# PCB_Plates_Combined_Eagle.net
KiCad netlist of a schematic drawn in EAGLE
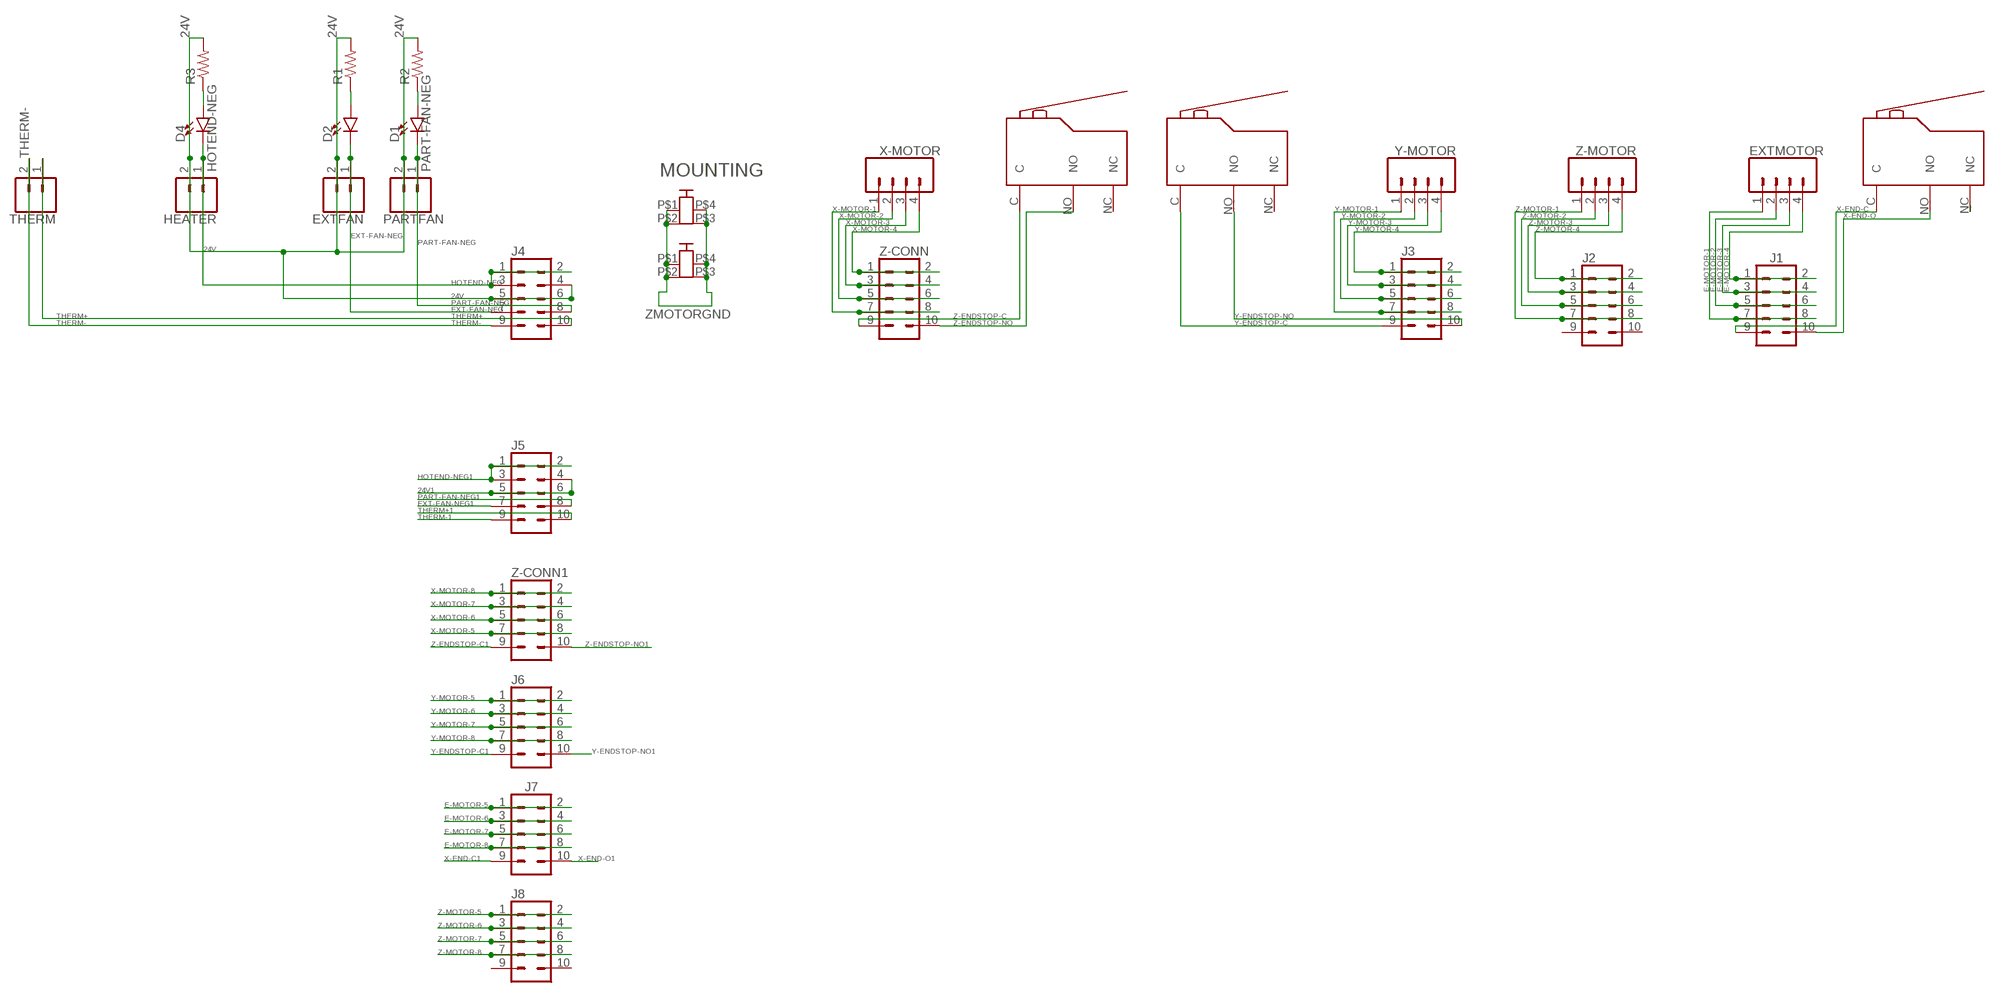
[diagram p0: schematic, sheet 1]

(export (version "E")
  (design (tool "Eeschema 10.0.6"))
  (components
    (comp (ref "CON1")
      (value "PCB-2M3")
      (footprint "eagle-import:PCB2-M3")
      (libsource (lib "eagle-import") (part "PCB-2M3"))
    )
    (comp (ref "CON7")
      (value "PCB-2M3")
      (footprint "eagle-import:PCB2-M3")
      (libsource (lib "eagle-import") (part "PCB-2M3"))
    )
    (comp (ref "D1")
      (value "LED-FKIT-1206")
      (footprint "eagle-import:FKIT-LED-1206")
      (libsource (lib "eagle-import") (part "LED-FKIT-1206"))
    )
    (comp (ref "D2")
      (value "LED-FKIT-1206")
      (footprint "eagle-import:FKIT-LED-1206")
      (libsource (lib "eagle-import") (part "LED-FKIT-1206"))
    )
    (comp (ref "D4")
      (value "LED-FKIT-1206")
      (footprint "eagle-import:FKIT-LED-1206")
      (libsource (lib "eagle-import") (part "LED-FKIT-1206"))
    )
    (comp (ref "EXTFAN")
      (value "CONN_023.5MM_LOCK")
      (footprint "eagle-import:SCREWTERMINAL-3.5MM-2_LOCK")
      (libsource (lib "eagle-import") (part "CONN_023.5MM_LOCK"))
    )
    (comp (ref "EXTMOTOR")
      (value "CONN_04SCREW_LOCK")
      (footprint "eagle-import:SCREWTERMINAL-3.5MM-4_LOCK")
      (libsource (lib "eagle-import") (part "CONN_04SCREW_LOCK"))
    )
    (comp (ref "HEATER")
      (value "CONN_023.5MM_LOCK")
      (footprint "eagle-import:SCREWTERMINAL-3.5MM-2_LOCK")
      (libsource (lib "eagle-import") (part "CONN_023.5MM_LOCK"))
    )
    (comp (ref "J1")
      (value "CONN_05X2SHD_LOCK")
      (footprint "eagle-import:2X5-SHROUDED_LOCK")
      (libsource (lib "eagle-import") (part "CONN_05X2SHD_LOCK"))
    )
    (comp (ref "J2")
      (value "CONN_05X2SHD_LOCK")
      (footprint "eagle-import:2X5-SHROUDED_LOCK")
      (libsource (lib "eagle-import") (part "CONN_05X2SHD_LOCK"))
    )
    (comp (ref "J3")
      (value "CONN_05X2SHD_LOCK")
      (footprint "eagle-import:2X5-SHROUDED_LOCK")
      (libsource (lib "eagle-import") (part "CONN_05X2SHD_LOCK"))
    )
    (comp (ref "J4")
      (value "CONN_05X2SHD_LOCK")
      (footprint "eagle-import:2X5-SHROUDED_LOCK")
      (libsource (lib "eagle-import") (part "CONN_05X2SHD_LOCK"))
    )
    (comp (ref "J5")
      (value "CONN_05X2SHD_LOCK")
      (footprint "eagle-import:2X5-SHROUDED_LOCK")
      (libsource (lib "eagle-import") (part "CONN_05X2SHD_LOCK"))
    )
    (comp (ref "J6")
      (value "CONN_05X2SHD_LOCK")
      (footprint "eagle-import:2X5-SHROUDED_LOCK")
      (libsource (lib "eagle-import") (part "CONN_05X2SHD_LOCK"))
    )
    (comp (ref "J7")
      (value "CONN_05X2SHD_LOCK")
      (footprint "eagle-import:2X5-SHROUDED_LOCK")
      (libsource (lib "eagle-import") (part "CONN_05X2SHD_LOCK"))
    )
    (comp (ref "J8")
      (value "CONN_05X2SHD_LOCK")
      (footprint "eagle-import:2X5-SHROUDED_LOCK")
      (libsource (lib "eagle-import") (part "CONN_05X2SHD_LOCK"))
    )
    (comp (ref "PARTFAN")
      (value "CONN_023.5MM_LOCK")
      (footprint "eagle-import:SCREWTERMINAL-3.5MM-2_LOCK")
      (libsource (lib "eagle-import") (part "CONN_023.5MM_LOCK"))
    )
    (comp (ref "R1")
      (value "R-US_R1206")
      (footprint "eagle-import:R1206")
      (libsource (lib "eagle-import") (part "R-US_R1206"))
    )
    (comp (ref "R2")
      (value "R-US_R1206")
      (footprint "eagle-import:R1206")
      (libsource (lib "eagle-import") (part "R-US_R1206"))
    )
    (comp (ref "R3")
      (value "R-US_R1206")
      (footprint "eagle-import:R1206")
      (libsource (lib "eagle-import") (part "R-US_R1206"))
    )
    (comp (ref "THERM")
      (value "CONN_023.5MM_LOCK")
      (footprint "eagle-import:SCREWTERMINAL-3.5MM-2_LOCK")
      (libsource (lib "eagle-import") (part "CONN_023.5MM_LOCK"))
    )
    (comp (ref "U$1")
      (value "Lever Microswitch Leftangle PCB mount, with Roller style lever, with a red roller")
      (footprint "eagle-import:LEVERMICROPCB-LEFTANGLE")
      (libsource (lib "eagle-import") (part "LEVERMICROPCBLEFTANGLE"))
    )
    (comp (ref "X-MOTOR")
      (value "CONN_04SCREW_LOCK")
      (footprint "eagle-import:SCREWTERMINAL-3.5MM-4_LOCK")
      (libsource (lib "eagle-import") (part "CONN_04SCREW_LOCK"))
    )
    (comp (ref "XENDSTOP")
      (value "Lever Microswitch Leftangle PCB mount, with Roller style lever, with a red roller")
      (footprint "eagle-import:LEVERMICROPCB-LEFTANGLE")
      (libsource (lib "eagle-import") (part "LEVERMICROPCBLEFTANGLE"))
    )
    (comp (ref "Y-MOTOR")
      (value "CONN_04SCREW_LOCK")
      (footprint "eagle-import:SCREWTERMINAL-3.5MM-4_LOCK")
      (libsource (lib "eagle-import") (part "CONN_04SCREW_LOCK"))
    )
    (comp (ref "Z-CONN")
      (value "CONN_05X2SHD_LOCK")
      (footprint "eagle-import:2X5-SHROUDED_LOCK")
      (libsource (lib "eagle-import") (part "CONN_05X2SHD_LOCK"))
    )
    (comp (ref "Z-CONN1")
      (value "CONN_05X2SHD_LOCK")
      (footprint "eagle-import:2X5-SHROUDED_LOCK")
      (libsource (lib "eagle-import") (part "CONN_05X2SHD_LOCK"))
    )
    (comp (ref "Z-MOTOR")
      (value "CONN_04SCREW_LOCK")
      (footprint "eagle-import:SCREWTERMINAL-3.5MM-4_LOCK")
      (libsource (lib "eagle-import") (part "CONN_04SCREW_LOCK"))
    )
    (comp (ref "ZENDSTOP")
      (value "Lever Microswitch Leftangle PCB mount, with Roller style lever, with a red roller")
      (footprint "eagle-import:LEVERMICROPCB-LEFTANGLE")
      (libsource (lib "eagle-import") (part "LEVERMICROPCBLEFTANGLE"))
    )
  )
  (nets
    (net (code "1") (name "/24V") (class "Default")
      (node (ref "EXTFAN") (pin "2") (pinfunction "2_2") (pintype "passive"))
      (node (ref "HEATER") (pin "2") (pinfunction "2_2") (pintype "passive"))
      (node (ref "J4") (pin "4") (pinfunction "4_4") (pintype "passive"))
      (node (ref "J4") (pin "5") (pinfunction "5_5") (pintype "passive"))
      (node (ref "J4") (pin "6") (pinfunction "6_6") (pintype "passive"))
      (node (ref "PARTFAN") (pin "2") (pinfunction "2_2") (pintype "passive"))
      (node (ref "R1") (pin "2") (pinfunction "2_2") (pintype "passive"))
      (node (ref "R2") (pin "2") (pinfunction "2_2") (pintype "passive"))
      (node (ref "R3") (pin "2") (pinfunction "2_2") (pintype "passive"))
    )
    (net (code "2") (name "/24V1") (class "Default")
      (node (ref "J5") (pin "4") (pinfunction "4_4") (pintype "passive"))
      (node (ref "J5") (pin "5") (pinfunction "5_5") (pintype "passive"))
      (node (ref "J5") (pin "6") (pinfunction "6_6") (pintype "passive"))
    )
    (net (code "3") (name "/E-MOTOR-1") (class "Default")
      (node (ref "EXTMOTOR") (pin "1") (pinfunction "1_1") (pintype "passive"))
      (node (ref "J1") (pin "7") (pinfunction "7_7") (pintype "passive"))
      (node (ref "J1") (pin "8") (pinfunction "8_8") (pintype "passive"))
    )
    (net (code "4") (name "/E-MOTOR-2") (class "Default")
      (node (ref "EXTMOTOR") (pin "2") (pinfunction "2_2") (pintype "passive"))
      (node (ref "J1") (pin "5") (pinfunction "5_5") (pintype "passive"))
      (node (ref "J1") (pin "6") (pinfunction "6_6") (pintype "passive"))
    )
    (net (code "5") (name "/E-MOTOR-3") (class "Default")
      (node (ref "EXTMOTOR") (pin "3") (pinfunction "3_3") (pintype "passive"))
      (node (ref "J1") (pin "3") (pinfunction "3_3") (pintype "passive"))
      (node (ref "J1") (pin "4") (pinfunction "4_4") (pintype "passive"))
    )
    (net (code "6") (name "/E-MOTOR-4") (class "Default")
      (node (ref "EXTMOTOR") (pin "4") (pinfunction "4_4") (pintype "passive"))
      (node (ref "J1") (pin "1") (pinfunction "1_1") (pintype "passive"))
      (node (ref "J1") (pin "2") (pinfunction "2_2") (pintype "passive"))
    )
    (net (code "7") (name "/E-MOTOR-5") (class "Default")
      (node (ref "J7") (pin "1") (pinfunction "1_1") (pintype "passive"))
      (node (ref "J7") (pin "2") (pinfunction "2_2") (pintype "passive"))
    )
    (net (code "8") (name "/E-MOTOR-6") (class "Default")
      (node (ref "J7") (pin "3") (pinfunction "3_3") (pintype "passive"))
      (node (ref "J7") (pin "4") (pinfunction "4_4") (pintype "passive"))
    )
    (net (code "9") (name "/E-MOTOR-7") (class "Default")
      (node (ref "J7") (pin "5") (pinfunction "5_5") (pintype "passive"))
      (node (ref "J7") (pin "6") (pinfunction "6_6") (pintype "passive"))
    )
    (net (code "10") (name "/E-MOTOR-8") (class "Default")
      (node (ref "J7") (pin "7") (pinfunction "7_7") (pintype "passive"))
      (node (ref "J7") (pin "8") (pinfunction "8_8") (pintype "passive"))
    )
    (net (code "11") (name "/EXT-FAN-NEG") (class "Default")
      (node (ref "D2") (pin "C") (pinfunction "C_C") (pintype "passive"))
      (node (ref "EXTFAN") (pin "1") (pinfunction "1_1") (pintype "passive"))
      (node (ref "J4") (pin "7") (pinfunction "7_7") (pintype "passive"))
    )
    (net (code "12") (name "/EXT-FAN-NEG1") (class "Default")
      (node (ref "J5") (pin "7") (pinfunction "7_7") (pintype "passive"))
    )
    (net (code "13") (name "/HOTEND-NEG") (class "Default")
      (node (ref "D4") (pin "C") (pinfunction "C_C") (pintype "passive"))
      (node (ref "HEATER") (pin "1") (pinfunction "1_1") (pintype "passive"))
      (node (ref "J4") (pin "1") (pinfunction "1_1") (pintype "passive"))
      (node (ref "J4") (pin "2") (pinfunction "2_2") (pintype "passive"))
      (node (ref "J4") (pin "3") (pinfunction "3_3") (pintype "passive"))
    )
    (net (code "14") (name "/HOTEND-NEG1") (class "Default")
      (node (ref "J5") (pin "1") (pinfunction "1_1") (pintype "passive"))
      (node (ref "J5") (pin "2") (pinfunction "2_2") (pintype "passive"))
      (node (ref "J5") (pin "3") (pinfunction "3_3") (pintype "passive"))
    )
    (net (code "15") (name "/PART-FAN-NEG") (class "Default")
      (node (ref "D1") (pin "C") (pinfunction "C_C") (pintype "passive"))
      (node (ref "J4") (pin "8") (pinfunction "8_8") (pintype "passive"))
      (node (ref "PARTFAN") (pin "1") (pinfunction "1_1") (pintype "passive"))
    )
    (net (code "16") (name "/PART-FAN-NEG1") (class "Default")
      (node (ref "J5") (pin "8") (pinfunction "8_8") (pintype "passive"))
    )
    (net (code "17") (name "/THERM+") (class "Default")
      (node (ref "J4") (pin "10") (pinfunction "10_10") (pintype "passive"))
      (node (ref "THERM") (pin "1") (pinfunction "1_1") (pintype "passive"))
    )
    (net (code "18") (name "/THERM+1") (class "Default")
      (node (ref "J5") (pin "10") (pinfunction "10_10") (pintype "passive"))
    )
    (net (code "19") (name "/THERM-") (class "Default")
      (node (ref "J4") (pin "9") (pinfunction "9_9") (pintype "passive"))
      (node (ref "THERM") (pin "2") (pinfunction "2_2") (pintype "passive"))
    )
    (net (code "20") (name "/THERM-1") (class "Default")
      (node (ref "J5") (pin "9") (pinfunction "9_9") (pintype "passive"))
    )
    (net (code "21") (name "/X-END-C") (class "Default")
      (node (ref "J1") (pin "9") (pinfunction "9_9") (pintype "passive"))
      (node (ref "XENDSTOP") (pin "C") (pinfunction "C_C") (pintype "bidirectional"))
    )
    (net (code "22") (name "/X-END-C1") (class "Default")
      (node (ref "J7") (pin "9") (pinfunction "9_9") (pintype "passive"))
    )
    (net (code "23") (name "/X-END-O") (class "Default")
      (node (ref "J1") (pin "10") (pinfunction "10_10") (pintype "passive"))
      (node (ref "XENDSTOP") (pin "NO") (pinfunction "NO_NO") (pintype "bidirectional"))
    )
    (net (code "24") (name "/X-END-O1") (class "Default")
      (node (ref "J7") (pin "10") (pinfunction "10_10") (pintype "passive"))
    )
    (net (code "25") (name "/X-MOTOR-1") (class "Default")
      (node (ref "X-MOTOR") (pin "1") (pinfunction "1_1") (pintype "passive"))
      (node (ref "Z-CONN") (pin "7") (pinfunction "7_7") (pintype "passive"))
      (node (ref "Z-CONN") (pin "8") (pinfunction "8_8") (pintype "passive"))
    )
    (net (code "26") (name "/X-MOTOR-2") (class "Default")
      (node (ref "X-MOTOR") (pin "2") (pinfunction "2_2") (pintype "passive"))
      (node (ref "Z-CONN") (pin "5") (pinfunction "5_5") (pintype "passive"))
      (node (ref "Z-CONN") (pin "6") (pinfunction "6_6") (pintype "passive"))
    )
    (net (code "27") (name "/X-MOTOR-3") (class "Default")
      (node (ref "X-MOTOR") (pin "3") (pinfunction "3_3") (pintype "passive"))
      (node (ref "Z-CONN") (pin "3") (pinfunction "3_3") (pintype "passive"))
      (node (ref "Z-CONN") (pin "4") (pinfunction "4_4") (pintype "passive"))
    )
    (net (code "28") (name "/X-MOTOR-4") (class "Default")
      (node (ref "X-MOTOR") (pin "4") (pinfunction "4_4") (pintype "passive"))
      (node (ref "Z-CONN") (pin "1") (pinfunction "1_1") (pintype "passive"))
      (node (ref "Z-CONN") (pin "2") (pinfunction "2_2") (pintype "passive"))
    )
    (net (code "29") (name "/X-MOTOR-5") (class "Default")
      (node (ref "Z-CONN1") (pin "7") (pinfunction "7_7") (pintype "passive"))
      (node (ref "Z-CONN1") (pin "8") (pinfunction "8_8") (pintype "passive"))
    )
    (net (code "30") (name "/X-MOTOR-6") (class "Default")
      (node (ref "Z-CONN1") (pin "5") (pinfunction "5_5") (pintype "passive"))
      (node (ref "Z-CONN1") (pin "6") (pinfunction "6_6") (pintype "passive"))
    )
    (net (code "31") (name "/X-MOTOR-7") (class "Default")
      (node (ref "Z-CONN1") (pin "3") (pinfunction "3_3") (pintype "passive"))
      (node (ref "Z-CONN1") (pin "4") (pinfunction "4_4") (pintype "passive"))
    )
    (net (code "32") (name "/X-MOTOR-8") (class "Default")
      (node (ref "Z-CONN1") (pin "1") (pinfunction "1_1") (pintype "passive"))
      (node (ref "Z-CONN1") (pin "2") (pinfunction "2_2") (pintype "passive"))
    )
    (net (code "33") (name "/Y-ENDSTOP-C") (class "Default")
      (node (ref "J3") (pin "9") (pinfunction "9_9") (pintype "passive"))
      (node (ref "U$1") (pin "C") (pinfunction "C_C") (pintype "bidirectional"))
    )
    (net (code "34") (name "/Y-ENDSTOP-C1") (class "Default")
      (node (ref "J6") (pin "9") (pinfunction "9_9") (pintype "passive"))
    )
    (net (code "35") (name "/Y-ENDSTOP-NO") (class "Default")
      (node (ref "J3") (pin "10") (pinfunction "10_10") (pintype "passive"))
      (node (ref "U$1") (pin "NO") (pinfunction "NO_NO") (pintype "bidirectional"))
    )
    (net (code "36") (name "/Y-ENDSTOP-NO1") (class "Default")
      (node (ref "J6") (pin "10") (pinfunction "10_10") (pintype "passive"))
    )
    (net (code "37") (name "/Y-MOTOR-1") (class "Default")
      (node (ref "J3") (pin "7") (pinfunction "7_7") (pintype "passive"))
      (node (ref "J3") (pin "8") (pinfunction "8_8") (pintype "passive"))
      (node (ref "Y-MOTOR") (pin "1") (pinfunction "1_1") (pintype "passive"))
    )
    (net (code "38") (name "/Y-MOTOR-2") (class "Default")
      (node (ref "J3") (pin "5") (pinfunction "5_5") (pintype "passive"))
      (node (ref "J3") (pin "6") (pinfunction "6_6") (pintype "passive"))
      (node (ref "Y-MOTOR") (pin "2") (pinfunction "2_2") (pintype "passive"))
    )
    (net (code "39") (name "/Y-MOTOR-3") (class "Default")
      (node (ref "J3") (pin "3") (pinfunction "3_3") (pintype "passive"))
      (node (ref "J3") (pin "4") (pinfunction "4_4") (pintype "passive"))
      (node (ref "Y-MOTOR") (pin "3") (pinfunction "3_3") (pintype "passive"))
    )
    (net (code "40") (name "/Y-MOTOR-4") (class "Default")
      (node (ref "J3") (pin "1") (pinfunction "1_1") (pintype "passive"))
      (node (ref "J3") (pin "2") (pinfunction "2_2") (pintype "passive"))
      (node (ref "Y-MOTOR") (pin "4") (pinfunction "4_4") (pintype "passive"))
    )
    (net (code "41") (name "/Y-MOTOR-5") (class "Default")
      (node (ref "J6") (pin "1") (pinfunction "1_1") (pintype "passive"))
      (node (ref "J6") (pin "2") (pinfunction "2_2") (pintype "passive"))
    )
    (net (code "42") (name "/Y-MOTOR-6") (class "Default")
      (node (ref "J6") (pin "3") (pinfunction "3_3") (pintype "passive"))
      (node (ref "J6") (pin "4") (pinfunction "4_4") (pintype "passive"))
    )
    (net (code "43") (name "/Y-MOTOR-7") (class "Default")
      (node (ref "J6") (pin "5") (pinfunction "5_5") (pintype "passive"))
      (node (ref "J6") (pin "6") (pinfunction "6_6") (pintype "passive"))
    )
    (net (code "44") (name "/Y-MOTOR-8") (class "Default")
      (node (ref "J6") (pin "7") (pinfunction "7_7") (pintype "passive"))
      (node (ref "J6") (pin "8") (pinfunction "8_8") (pintype "passive"))
    )
    (net (code "45") (name "/Z-ENDSTOP-C") (class "Default")
      (node (ref "Z-CONN") (pin "9") (pinfunction "9_9") (pintype "passive"))
      (node (ref "ZENDSTOP") (pin "C") (pinfunction "C_C") (pintype "bidirectional"))
    )
    (net (code "46") (name "/Z-ENDSTOP-C1") (class "Default")
      (node (ref "Z-CONN1") (pin "9") (pinfunction "9_9") (pintype "passive"))
    )
    (net (code "47") (name "/Z-ENDSTOP-NO") (class "Default")
      (node (ref "Z-CONN") (pin "10") (pinfunction "10_10") (pintype "passive"))
      (node (ref "ZENDSTOP") (pin "NO") (pinfunction "NO_NO") (pintype "bidirectional"))
    )
    (net (code "48") (name "/Z-ENDSTOP-NO1") (class "Default")
      (node (ref "Z-CONN1") (pin "10") (pinfunction "10_10") (pintype "passive"))
    )
    (net (code "49") (name "/Z-MOTOR-1") (class "Default")
      (node (ref "J2") (pin "7") (pinfunction "7_7") (pintype "passive"))
      (node (ref "J2") (pin "8") (pinfunction "8_8") (pintype "passive"))
      (node (ref "Z-MOTOR") (pin "1") (pinfunction "1_1") (pintype "passive"))
    )
    (net (code "50") (name "/Z-MOTOR-2") (class "Default")
      (node (ref "J2") (pin "5") (pinfunction "5_5") (pintype "passive"))
      (node (ref "J2") (pin "6") (pinfunction "6_6") (pintype "passive"))
      (node (ref "Z-MOTOR") (pin "2") (pinfunction "2_2") (pintype "passive"))
    )
    (net (code "51") (name "/Z-MOTOR-3") (class "Default")
      (node (ref "J2") (pin "3") (pinfunction "3_3") (pintype "passive"))
      (node (ref "J2") (pin "4") (pinfunction "4_4") (pintype "passive"))
      (node (ref "Z-MOTOR") (pin "3") (pinfunction "3_3") (pintype "passive"))
    )
    (net (code "52") (name "/Z-MOTOR-4") (class "Default")
      (node (ref "J2") (pin "1") (pinfunction "1_1") (pintype "passive"))
      (node (ref "J2") (pin "2") (pinfunction "2_2") (pintype "passive"))
      (node (ref "Z-MOTOR") (pin "4") (pinfunction "4_4") (pintype "passive"))
    )
    (net (code "53") (name "/Z-MOTOR-5") (class "Default")
      (node (ref "J8") (pin "1") (pinfunction "1_1") (pintype "passive"))
      (node (ref "J8") (pin "2") (pinfunction "2_2") (pintype "passive"))
    )
    (net (code "54") (name "/Z-MOTOR-6") (class "Default")
      (node (ref "J8") (pin "3") (pinfunction "3_3") (pintype "passive"))
      (node (ref "J8") (pin "4") (pinfunction "4_4") (pintype "passive"))
    )
    (net (code "55") (name "/Z-MOTOR-7") (class "Default")
      (node (ref "J8") (pin "5") (pinfunction "5_5") (pintype "passive"))
      (node (ref "J8") (pin "6") (pinfunction "6_6") (pintype "passive"))
    )
    (net (code "56") (name "/Z-MOTOR-8") (class "Default")
      (node (ref "J8") (pin "7") (pinfunction "7_7") (pintype "passive"))
      (node (ref "J8") (pin "8") (pinfunction "8_8") (pintype "passive"))
    )
    (net (code "57") (name "/ZMOTORGND") (class "Default")
      (node (ref "CON1") (pin "P$1") (pinfunction "P$1_P$1") (pintype "bidirectional"))
      (node (ref "CON1") (pin "P$2") (pinfunction "P$2_P$2") (pintype "bidirectional"))
      (node (ref "CON1") (pin "P$3") (pinfunction "P$3_P$3") (pintype "bidirectional"))
      (node (ref "CON1") (pin "P$4") (pinfunction "P$4_P$4") (pintype "bidirectional"))
      (node (ref "CON7") (pin "P$1") (pinfunction "P$1_P$1") (pintype "bidirectional"))
      (node (ref "CON7") (pin "P$2") (pinfunction "P$2_P$2") (pintype "bidirectional"))
      (node (ref "CON7") (pin "P$3") (pinfunction "P$3_P$3") (pintype "bidirectional"))
      (node (ref "CON7") (pin "P$4") (pinfunction "P$4_P$4") (pintype "bidirectional"))
    )
    (net (code "58") (name "Net-(D1-PadA)") (class "Default")
      (node (ref "D1") (pin "A") (pinfunction "A_A") (pintype "passive"))
      (node (ref "R2") (pin "1") (pinfunction "1_1") (pintype "passive"))
    )
    (net (code "59") (name "Net-(D2-PadA)") (class "Default")
      (node (ref "D2") (pin "A") (pinfunction "A_A") (pintype "passive"))
      (node (ref "R1") (pin "1") (pinfunction "1_1") (pintype "passive"))
    )
    (net (code "60") (name "Net-(D4-PadA)") (class "Default")
      (node (ref "D4") (pin "A") (pinfunction "A_A") (pintype "passive"))
      (node (ref "R3") (pin "1") (pinfunction "1_1") (pintype "passive"))
    )
    (net (code "61") (name "unconnected-(J2-Pad9)") (class "Default")
      (node (ref "J2") (pin "9") (pinfunction "9_9") (pintype "passive"))
    )
    (net (code "62") (name "unconnected-(J2-Pad10)") (class "Default")
      (node (ref "J2") (pin "10") (pinfunction "10_10") (pintype "passive"))
    )
    (net (code "63") (name "unconnected-(J8-Pad9)") (class "Default")
      (node (ref "J8") (pin "9") (pinfunction "9_9") (pintype "passive"))
    )
    (net (code "64") (name "unconnected-(J8-Pad10)") (class "Default")
      (node (ref "J8") (pin "10") (pinfunction "10_10") (pintype "passive"))
    )
    (net (code "65") (name "unconnected-(U$1-PadNC)") (class "Default")
      (node (ref "U$1") (pin "NC") (pinfunction "NC_NC") (pintype "bidirectional"))
    )
    (net (code "66") (name "unconnected-(XENDSTOP-PadNC)") (class "Default")
      (node (ref "XENDSTOP") (pin "NC") (pinfunction "NC_NC") (pintype "bidirectional"))
    )
    (net (code "67") (name "unconnected-(ZENDSTOP-PadNC)") (class "Default")
      (node (ref "ZENDSTOP") (pin "NC") (pinfunction "NC_NC") (pintype "bidirectional"))
    )
  )
)
